# LED_Driver_NE2G757GT.net
KiCad netlist of a schematic drawn in Altium Designer
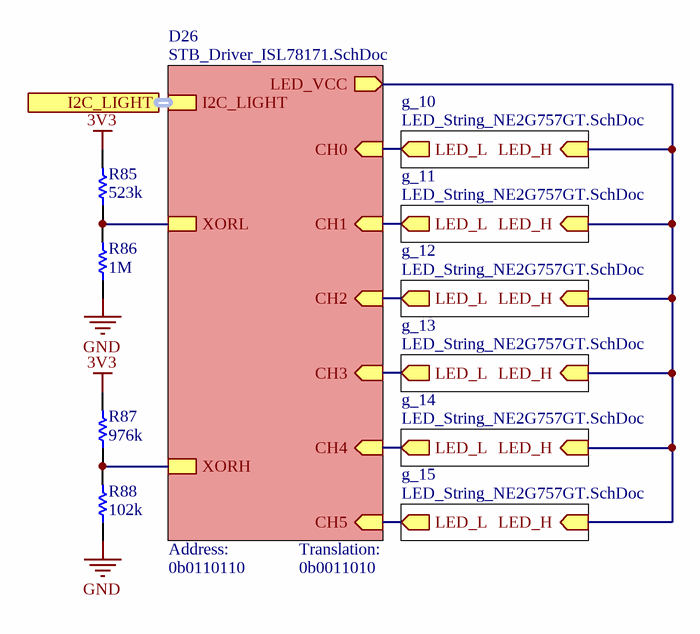
[diagram p0: LED_Driver_NE2G757GT.SchDoc]

(export (version "E")
  (design (tool "Eeschema 10.0.6"))
  (components
    (comp (ref "R85")
      (value "523k")
      (footprint "RESC1005X40X25LL05T05")
      (fields
        (field (name "MANUFACTURER") "Panasonic")
        (field (name "PART NUMBER") "ERJ-2RKF5233X")
        (field (name "TOLERANCE") "1%")
      )
      (libsource (lib "Altium Content Vault") (part "RES"))
    )
    (comp (ref "R86")
      (value "1M")
      (footprint "RESC1005X40X25LL05T05")
      (description "Chip Resistor, 1 MOhm, +/- 1%, 100 mW, -55 to 155 degC, 0402 (1005 Metric), RoHS, Tape and Reel")
      (fields (field (name "PARTNUMBER") "ERJ-2RKF1004X") (field (name "TOLERANCE") "1%"))
      (libsource (lib "Altium Content Vault") (part "RES-2"))
    )
    (comp (ref "R87")
      (value "976k")
      (footprint "RESC1005X40X25LL05T05")
      (fields
        (field (name "MANUFACTURER") "Panasonic")
        (field (name "PART NUMBER") "ERJ-2RKF9763X")
        (field (name "TOLERANCE") "1%")
      )
      (libsource (lib "Altium Content Vault") (part "RES"))
    )
    (comp (ref "R88")
      (value "102k")
      (footprint "RESC1005X40X25LL05T05")
      (fields
        (field (name "MANUFACTURER") "Panasonic")
        (field (name "PART NUMBER") "ERJ-2RKF1023X")
        (field (name "TOLERANCE") "1%")
      )
      (libsource (lib "Altium Content Vault") (part "RES"))
    )
  )
  (nets
    (net (code "10") (name "/XORH") (class "Default")
      (node (ref "R87") (pin "1") (pinfunction "1_1") (pintype "passive"))
      (node (ref "R88") (pin "2") (pinfunction "2_2") (pintype "passive"))
    )
    (net (code "11") (name "/XORL") (class "Default")
      (node (ref "R85") (pin "1") (pinfunction "1_1") (pintype "passive"))
      (node (ref "R86") (pin "2") (pinfunction "2_2") (pintype "passive"))
    )
    (net (code "12") (name "3V3") (class "Default")
      (node (ref "R85") (pin "2") (pinfunction "2_2") (pintype "passive"))
      (node (ref "R87") (pin "2") (pinfunction "2_2") (pintype "passive"))
    )
    (net (code "13") (name "GND") (class "Default")
      (node (ref "R86") (pin "1") (pinfunction "1_1") (pintype "passive"))
      (node (ref "R88") (pin "1") (pinfunction "1_1") (pintype "passive"))
    )
  )
)
